# Lone_Sleeper.net
KiCad netlist of a schematic drawn in EAGLE
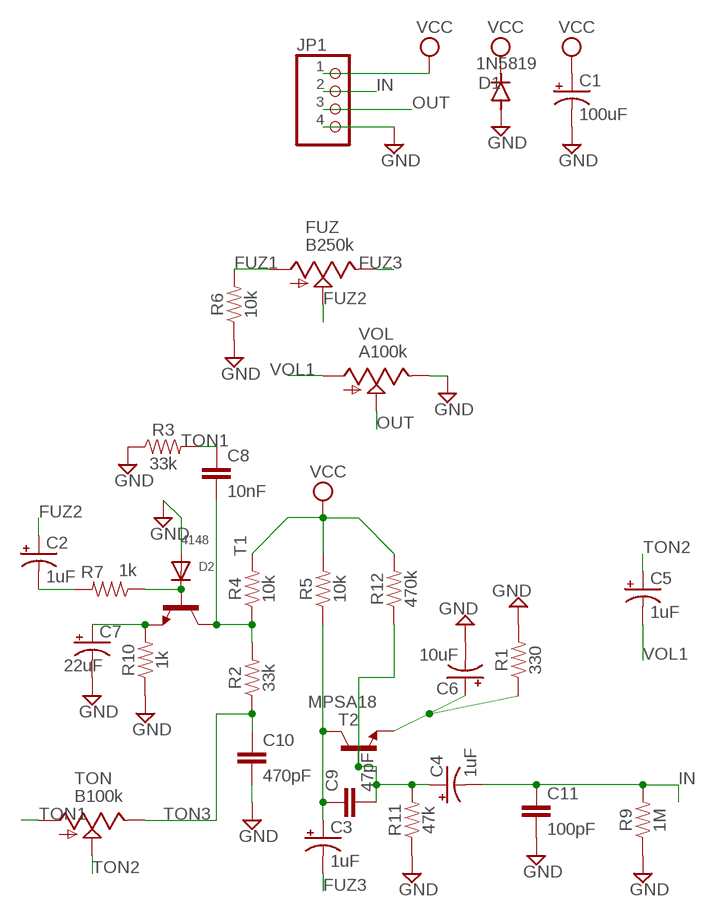
[diagram p0: schematic, sheet 1]

(export (version "E")
  (design (tool "Eeschema 10.0.6"))
  (components
    (comp (ref "C1")
      (value "100uF")
      (footprint "eagle-import:PAN_B_SMD+THRU")
      (libsource (lib "eagle-import") (part "CAP_SMD+THRUPAN_B"))
    )
    (comp (ref "C2")
      (value "1uF")
      (footprint "eagle-import:PAN_B_SMD+THRU")
      (libsource (lib "eagle-import") (part "CAP_SMD+THRUPAN_B"))
    )
    (comp (ref "C3")
      (value "1uF")
      (footprint "eagle-import:PAN_B_SMD+THRU")
      (libsource (lib "eagle-import") (part "CAP_SMD+THRUPAN_B"))
    )
    (comp (ref "C4")
      (value "1uF")
      (footprint "eagle-import:PAN_B_SMD+THRU")
      (libsource (lib "eagle-import") (part "CAP_SMD+THRUPAN_B"))
    )
    (comp (ref "C5")
      (value "1uF")
      (footprint "eagle-import:PAN_B_SMD+THRU")
      (libsource (lib "eagle-import") (part "CAP_SMD+THRUPAN_B"))
    )
    (comp (ref "C6")
      (value "10uF")
      (footprint "eagle-import:PAN_B_SMD+THRU")
      (libsource (lib "eagle-import") (part "CAP_SMD+THRUPAN_B"))
    )
    (comp (ref "C7")
      (value "22uF")
      (footprint "eagle-import:PAN_B_SMD+THRU")
      (libsource (lib "eagle-import") (part "CAP_SMD+THRUPAN_B"))
    )
    (comp (ref "C8")
      (value "10nF")
      (footprint "eagle-import:0603")
      (libsource (lib "eagle-import") (part "10NF-0603-50V-10%"))
    )
    (comp (ref "C9")
      (value "47pF")
      (footprint "eagle-import:0603")
      (libsource (lib "eagle-import") (part "47PF-0603-50V-5%"))
    )
    (comp (ref "C10")
      (value "470pF")
      (footprint "eagle-import:0603")
      (libsource (lib "eagle-import") (part "470PF-0603-50V-5%"))
    )
    (comp (ref "C11")
      (value "100pF")
      (footprint "eagle-import:0603")
      (libsource (lib "eagle-import") (part "100PF-0603-50V-5%"))
    )
    (comp (ref "D1")
      (value "1N5819")
      (footprint "eagle-import:SOD123")
      (libsource (lib "eagle-import") (part "DIODE-SOD123"))
    )
    (comp (ref "D2")
      (value "4148")
      (footprint "eagle-import:SOD-123")
      (libsource (lib "eagle-import") (part "DIODESOD-123"))
    )
    (comp (ref "FUZ")
      (value "B250k")
      (footprint "eagle-import:9MM_SNAP-IN_POT")
      (libsource (lib "eagle-import") (part "9MM_SNAP-IN_POT_"))
    )
    (comp (ref "JP1")
      (value "PINHD-1X4")
      (footprint "eagle-import:1X04")
      (libsource (lib "eagle-import") (part "PINHD-1X4"))
    )
    (comp (ref "R1")
      (value "330")
      (footprint "eagle-import:0603")
      (libsource (lib "eagle-import") (part "330OHM-0603-1/10W-1%"))
    )
    (comp (ref "R2")
      (value "33k")
      (footprint "eagle-import:0603")
      (libsource (lib "eagle-import") (part "33KOHM-0603-1/10W-1%"))
    )
    (comp (ref "R3")
      (value "33k")
      (footprint "eagle-import:0603")
      (libsource (lib "eagle-import") (part "33KOHM-0603-1/10W-1%"))
    )
    (comp (ref "R4")
      (value "10k")
      (footprint "eagle-import:0603")
      (libsource (lib "eagle-import") (part "10KOHM-0603-1/10W-1%"))
    )
    (comp (ref "R5")
      (value "10k")
      (footprint "eagle-import:0603")
      (libsource (lib "eagle-import") (part "10KOHM-0603-1/10W-1%"))
    )
    (comp (ref "R6")
      (value "10k")
      (footprint "eagle-import:0603")
      (libsource (lib "eagle-import") (part "10KOHM-0603-1/10W-1%"))
    )
    (comp (ref "R7")
      (value "1k")
      (footprint "eagle-import:0603")
      (libsource (lib "eagle-import") (part "1KOHM-0603-1/10W-1%"))
    )
    (comp (ref "R9")
      (value "1M")
      (footprint "eagle-import:0603")
      (libsource (lib "eagle-import") (part "1MOHM-0603-1/4W-5%"))
    )
    (comp (ref "R10")
      (value "1k")
      (footprint "eagle-import:0603")
      (libsource (lib "eagle-import") (part "1KOHM-0603-1/10W-1%"))
    )
    (comp (ref "R11")
      (value "47k")
      (footprint "eagle-import:0603")
      (libsource (lib "eagle-import") (part "47KOHM-0603-1/10W-1%"))
    )
    (comp (ref "R12")
      (value "470k")
      (footprint "eagle-import:0603")
      (libsource (lib "eagle-import") (part "RESISTOR0603"))
    )
    (comp (ref "T1")
      (value "-NPN-TO5")
      (footprint "eagle-import:TO5")
      (libsource (lib "eagle-import") (part "-NPN-TO5"))
    )
    (comp (ref "T2")
      (value "MPSA18")
      (footprint "eagle-import:TO92-EBC")
      (libsource (lib "eagle-import") (part "-NPN-TO92-EBC"))
    )
    (comp (ref "TON")
      (value "B100k")
      (footprint "eagle-import:9MM_SNAP-IN_POT")
      (libsource (lib "eagle-import") (part "9MM_SNAP-IN_POT_"))
    )
    (comp (ref "VOL")
      (value "A100k")
      (footprint "eagle-import:9MM_SNAP-IN_POT")
      (libsource (lib "eagle-import") (part "9MM_SNAP-IN_POT_"))
    )
  )
  (nets
    (net (code "1") (name "/FUZ1") (class "Default")
      (node (ref "FUZ") (pin "1") (pinfunction "A_1") (pintype "passive"))
      (node (ref "R6") (pin "2") (pinfunction "2_2") (pintype "passive"))
    )
    (net (code "2") (name "/FUZ2") (class "Default")
      (node (ref "C2") (pin "+") (pinfunction "+_+") (pintype "passive"))
      (node (ref "C2") (pin "++") (pinfunction "+_++") (pintype "passive"))
      (node (ref "FUZ") (pin "2") (pinfunction "S_2") (pintype "passive"))
    )
    (net (code "3") (name "/FUZ3") (class "Default")
      (node (ref "C3") (pin "-") (pinfunction "-_-") (pintype "passive"))
      (node (ref "C3") (pin "--") (pinfunction "-_--") (pintype "passive"))
      (node (ref "FUZ") (pin "3") (pinfunction "E_3") (pintype "passive"))
    )
    (net (code "4") (name "/IN") (class "Default")
      (node (ref "C11") (pin "1") (pinfunction "1_1") (pintype "passive"))
      (node (ref "C4") (pin "-") (pinfunction "-_-") (pintype "passive"))
      (node (ref "C4") (pin "--") (pinfunction "-_--") (pintype "passive"))
      (node (ref "JP1") (pin "2") (pinfunction "2_2") (pintype "passive"))
      (node (ref "R9") (pin "2") (pinfunction "2_2") (pintype "passive"))
    )
    (net (code "5") (name "/OUT") (class "Default")
      (node (ref "JP1") (pin "3") (pinfunction "3_3") (pintype "passive"))
      (node (ref "VOL") (pin "2") (pinfunction "S_2") (pintype "passive"))
    )
    (net (code "6") (name "/TON1") (class "Default")
      (node (ref "C8") (pin "1") (pinfunction "1_1") (pintype "passive"))
      (node (ref "R3") (pin "2") (pinfunction "2_2") (pintype "passive"))
      (node (ref "TON") (pin "1") (pinfunction "A_1") (pintype "passive"))
    )
    (net (code "7") (name "/TON2") (class "Default")
      (node (ref "C5") (pin "+") (pinfunction "+_+") (pintype "passive"))
      (node (ref "C5") (pin "++") (pinfunction "+_++") (pintype "passive"))
      (node (ref "TON") (pin "2") (pinfunction "S_2") (pintype "passive"))
    )
    (net (code "8") (name "/TON3") (class "Default")
      (node (ref "C10") (pin "1") (pinfunction "1_1") (pintype "passive"))
      (node (ref "R2") (pin "1") (pinfunction "1_1") (pintype "passive"))
      (node (ref "TON") (pin "3") (pinfunction "E_3") (pintype "passive"))
    )
    (net (code "9") (name "/VOL1") (class "Default")
      (node (ref "C5") (pin "-") (pinfunction "-_-") (pintype "passive"))
      (node (ref "C5") (pin "--") (pinfunction "-_--") (pintype "passive"))
      (node (ref "VOL") (pin "1") (pinfunction "A_1") (pintype "passive"))
    )
    (net (code "10") (name "GND") (class "Default")
      (node (ref "C1") (pin "-") (pinfunction "-_-") (pintype "passive"))
      (node (ref "C1") (pin "--") (pinfunction "-_--") (pintype "passive"))
      (node (ref "C10") (pin "2") (pinfunction "2_2") (pintype "passive"))
      (node (ref "C11") (pin "2") (pinfunction "2_2") (pintype "passive"))
      (node (ref "C6") (pin "-") (pinfunction "-_-") (pintype "passive"))
      (node (ref "C6") (pin "--") (pinfunction "-_--") (pintype "passive"))
      (node (ref "C7") (pin "-") (pinfunction "-_-") (pintype "passive"))
      (node (ref "C7") (pin "--") (pinfunction "-_--") (pintype "passive"))
      (node (ref "D1") (pin "A") (pinfunction "A_A") (pintype "passive"))
      (node (ref "D2") (pin "A") (pinfunction "A_A") (pintype "passive"))
      (node (ref "JP1") (pin "4") (pinfunction "4_4") (pintype "passive"))
      (node (ref "R1") (pin "2") (pinfunction "2_2") (pintype "passive"))
      (node (ref "R10") (pin "1") (pinfunction "1_1") (pintype "passive"))
      (node (ref "R11") (pin "1") (pinfunction "1_1") (pintype "passive"))
      (node (ref "R3") (pin "1") (pinfunction "1_1") (pintype "passive"))
      (node (ref "R6") (pin "1") (pinfunction "1_1") (pintype "passive"))
      (node (ref "R9") (pin "1") (pinfunction "1_1") (pintype "passive"))
      (node (ref "VOL") (pin "3") (pinfunction "E_3") (pintype "passive"))
    )
    (net (code "11") (name "Net-(C2---Pad--)") (class "Default")
      (node (ref "C2") (pin "-") (pinfunction "-_-") (pintype "passive"))
      (node (ref "C2") (pin "--") (pinfunction "-_--") (pintype "passive"))
      (node (ref "R7") (pin "2") (pinfunction "2_2") (pintype "passive"))
    )
    (net (code "12") (name "Net-(C3-+-Pad++)") (class "Default")
      (node (ref "C3") (pin "+") (pinfunction "+_+") (pintype "passive"))
      (node (ref "C3") (pin "++") (pinfunction "+_++") (pintype "passive"))
      (node (ref "C9") (pin "1") (pinfunction "1_1") (pintype "passive"))
      (node (ref "R5") (pin "1") (pinfunction "1_1") (pintype "passive"))
      (node (ref "T2") (pin "C") (pinfunction "C_C") (pintype "passive"))
    )
    (net (code "13") (name "Net-(C4-+-Pad++)") (class "Default")
      (node (ref "C4") (pin "+") (pinfunction "+_+") (pintype "passive"))
      (node (ref "C4") (pin "++") (pinfunction "+_++") (pintype "passive"))
      (node (ref "C9") (pin "2") (pinfunction "2_2") (pintype "passive"))
      (node (ref "R11") (pin "2") (pinfunction "2_2") (pintype "passive"))
      (node (ref "R12") (pin "1") (pinfunction "1_1") (pintype "passive"))
      (node (ref "T2") (pin "B") (pinfunction "B_B") (pintype "passive"))
    )
    (net (code "14") (name "Net-(C6-+-Pad++)") (class "Default")
      (node (ref "C6") (pin "+") (pinfunction "+_+") (pintype "passive"))
      (node (ref "C6") (pin "++") (pinfunction "+_++") (pintype "passive"))
      (node (ref "R1") (pin "1") (pinfunction "1_1") (pintype "passive"))
      (node (ref "T2") (pin "E") (pinfunction "E_E") (pintype "passive"))
    )
    (net (code "15") (name "Net-(T1-B)") (class "Default")
      (node (ref "D2") (pin "C") (pinfunction "C_C") (pintype "passive"))
      (node (ref "R7") (pin "1") (pinfunction "1_1") (pintype "passive"))
      (node (ref "T1") (pin "2") (pinfunction "B_2") (pintype "passive"))
    )
    (net (code "16") (name "Net-(T1-C)") (class "Default")
      (node (ref "C8") (pin "2") (pinfunction "2_2") (pintype "passive"))
      (node (ref "R2") (pin "2") (pinfunction "2_2") (pintype "passive"))
      (node (ref "R4") (pin "1") (pinfunction "1_1") (pintype "passive"))
      (node (ref "T1") (pin "3") (pinfunction "C_3") (pintype "passive"))
    )
    (net (code "17") (name "Net-(T1-E)") (class "Default")
      (node (ref "C7") (pin "+") (pinfunction "+_+") (pintype "passive"))
      (node (ref "C7") (pin "++") (pinfunction "+_++") (pintype "passive"))
      (node (ref "R10") (pin "2") (pinfunction "2_2") (pintype "passive"))
      (node (ref "T1") (pin "1") (pinfunction "E_1") (pintype "passive"))
    )
    (net (code "18") (name "VCC") (class "Default")
      (node (ref "C1") (pin "+") (pinfunction "+_+") (pintype "passive"))
      (node (ref "C1") (pin "++") (pinfunction "+_++") (pintype "passive"))
      (node (ref "D1") (pin "C") (pinfunction "C_C") (pintype "passive"))
      (node (ref "JP1") (pin "1") (pinfunction "1_1") (pintype "passive"))
      (node (ref "R12") (pin "2") (pinfunction "2_2") (pintype "passive"))
      (node (ref "R4") (pin "2") (pinfunction "2_2") (pintype "passive"))
      (node (ref "R5") (pin "2") (pinfunction "2_2") (pintype "passive"))
    )
  )
)
